# CharliesAlienWhoopF4.net
KiCad netlist of a schematic drawn in EAGLE
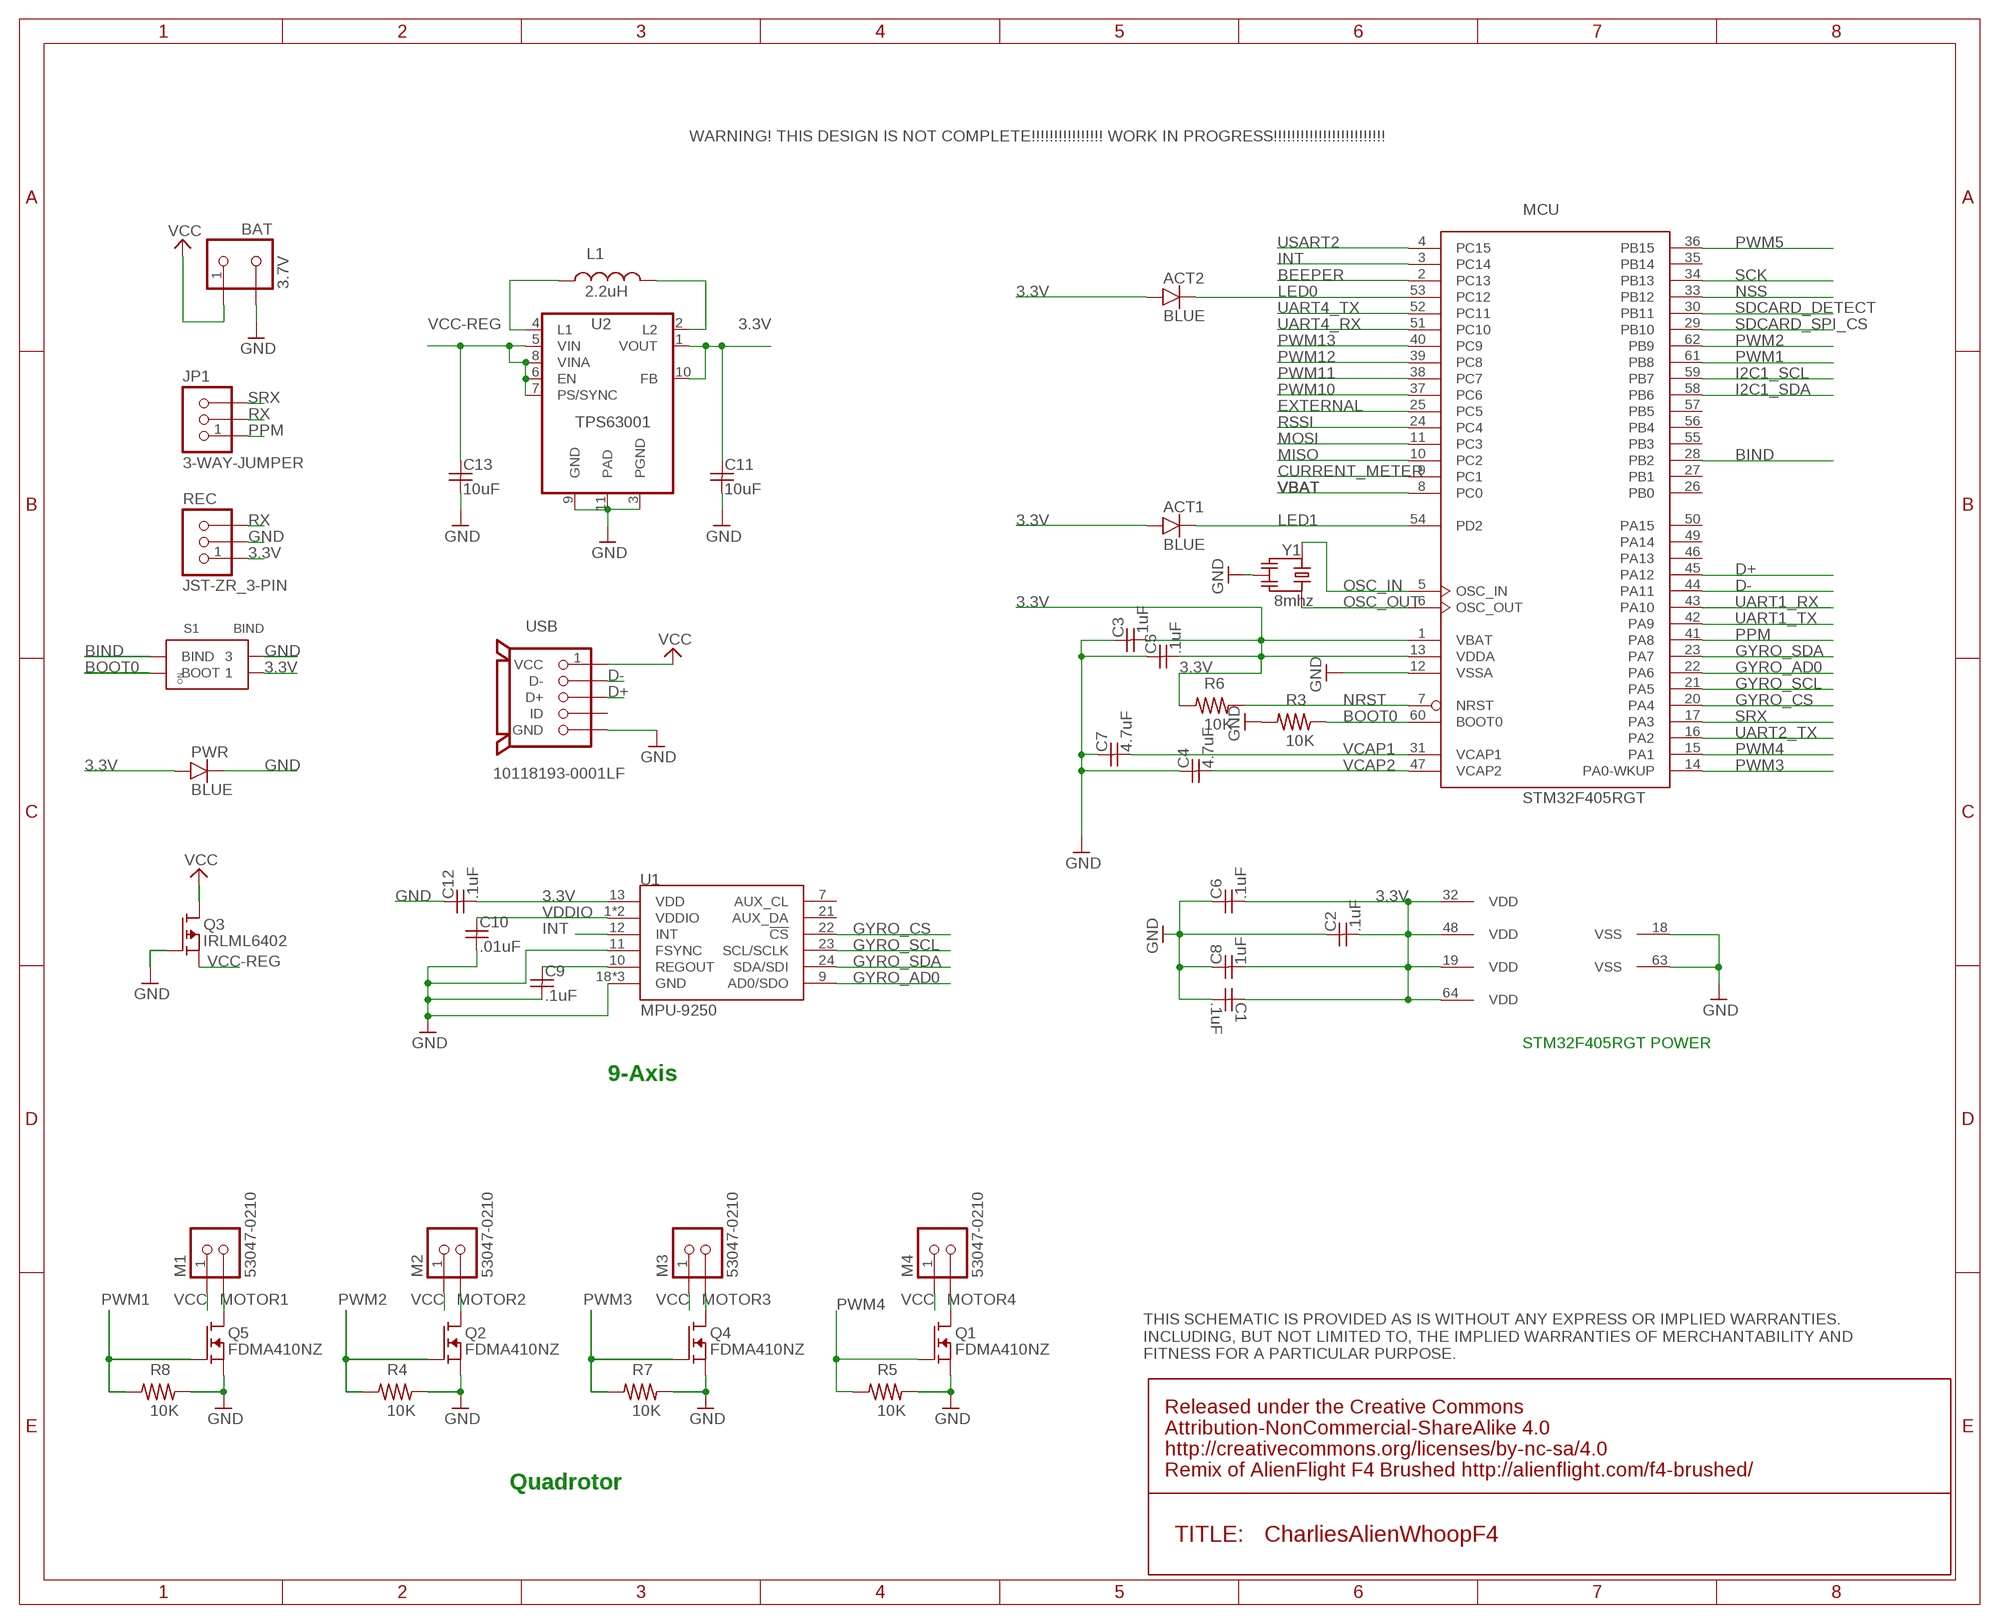
[diagram p0: schematic, sheet 1]

(export (version "E")
  (design (tool "Eeschema 10.0.6"))
  (components
    (comp (ref "ACT1")
      (value "BLUE")
      (footprint "eagle-import:SMD-CHIP-LED-0805")
      (fields (field (name "MF") "Kingbright") (field (name "MPN") "APHCM2012QBC/D-F01"))
      (libsource (lib "eagle-import") (part "SMD-CHIP-LED-0805"))
    )
    (comp (ref "ACT2")
      (value "BLUE")
      (footprint "eagle-import:SMD-CHIP-LED-0805")
      (fields (field (name "MF") "Kingbright") (field (name "MPN") "APHCM2012QBC/D-F01"))
      (libsource (lib "eagle-import") (part "SMD-CHIP-LED-0805"))
    )
    (comp (ref "BAT")
      (value "3.7V")
      (footprint "eagle-import:S2B-PH-K-S")
      (fields (field (name "MF") "JST") (field (name "MPN") "S2B-PH-K-S"))
      (libsource (lib "eagle-import") (part "JST-PH-BAT"))
    )
    (comp (ref "C1")
      (value ".1uF")
      (footprint "eagle-import:MUR-CAP-0603")
      (fields (field (name "MF") "Murata") (field (name "MPN") "GRM188R71C104KA01D"))
      (libsource (lib "eagle-import") (part "CAPACITOR.1UF"))
    )
    (comp (ref "C2")
      (value ".1uF")
      (footprint "eagle-import:MUR-CAP-0603")
      (fields (field (name "MF") "Murata") (field (name "MPN") "GRM188R71C104KA01D"))
      (libsource (lib "eagle-import") (part "CAPACITOR.1UF"))
    )
    (comp (ref "C3")
      (value ".1uF")
      (footprint "eagle-import:MUR-CAP-0603")
      (fields (field (name "MF") "Murata") (field (name "MPN") "GRM188R71C104KA01D"))
      (libsource (lib "eagle-import") (part "CAPACITOR.1UF"))
    )
    (comp (ref "C4")
      (value "4.7uF")
      (footprint "eagle-import:MUR-CAP-0603")
      (fields (field (name "MF") "Murata") (field (name "MPN") "GRJ188C70J475KE11D"))
      (libsource (lib "eagle-import") (part "CAPACITOR4.7UF"))
    )
    (comp (ref "C5")
      (value ".1uF")
      (footprint "eagle-import:MUR-CAP-0603")
      (fields (field (name "MF") "Murata") (field (name "MPN") "GRM188R71C104KA01D"))
      (libsource (lib "eagle-import") (part "CAPACITOR.1UF"))
    )
    (comp (ref "C6")
      (value ".1uF")
      (footprint "eagle-import:MUR-CAP-0603")
      (fields (field (name "MF") "Murata") (field (name "MPN") "GRM188R71C104KA01D"))
      (libsource (lib "eagle-import") (part "CAPACITOR.1UF"))
    )
    (comp (ref "C7")
      (value "4.7uF")
      (footprint "eagle-import:MUR-CAP-0603")
      (fields (field (name "MF") "Murata") (field (name "MPN") "GRJ188C70J475KE11D"))
      (libsource (lib "eagle-import") (part "CAPACITOR4.7UF"))
    )
    (comp (ref "C8")
      (value "1uF")
      (footprint "eagle-import:MUR-CAP-0603")
      (fields (field (name "MF") "Murata") (field (name "MPN") "GRM188R71C105KA12D"))
      (libsource (lib "eagle-import") (part "CAPACITOR1UF"))
    )
    (comp (ref "C9")
      (value ".1uF")
      (footprint "eagle-import:MUR-CAP-0603")
      (fields (field (name "MF") "Murata") (field (name "MPN") "GRM188R71C104KA01D"))
      (libsource (lib "eagle-import") (part "CAPACITOR.1UF"))
    )
    (comp (ref "C10")
      (value ".01uF")
      (footprint "eagle-import:MUR-CAP-0603")
      (fields (field (name "MF") "Murata") (field (name "MPN") "GRM188R71C103KA01D"))
      (libsource (lib "eagle-import") (part "CAPACITOR.01UF"))
    )
    (comp (ref "C11")
      (value "10uF")
      (footprint "eagle-import:YUDEN-CAP-0805")
      (fields (field (name "MF") "Taiyo Yuden") (field (name "MPN") "JMK212AB7106KG-T"))
      (libsource (lib "eagle-import") (part "CAPACITOR10UF"))
    )
    (comp (ref "C12")
      (value ".1uF")
      (footprint "eagle-import:MUR-CAP-0603")
      (fields (field (name "MF") "Murata") (field (name "MPN") "GRM188R71C104KA01D"))
      (libsource (lib "eagle-import") (part "CAPACITOR.1UF"))
    )
    (comp (ref "C13")
      (value "10uF")
      (footprint "eagle-import:YUDEN-CAP-0805")
      (fields (field (name "MF") "Taiyo Yuden") (field (name "MPN") "JMK212AB7106KG-T"))
      (libsource (lib "eagle-import") (part "CAPACITOR10UF"))
    )
    (comp (ref "JP1")
      (value "3-WAY-JUMPER")
      (footprint "eagle-import:3-WAY-JUMPER")
      (libsource (lib "eagle-import") (part "3-WAY-JUMPER"))
    )
    (comp (ref "L1")
      (value "2.2uH")
      (footprint "eagle-import:NR301X")
      (fields (field (name "MF") "Taiyo Yuden") (field (name "MPN") "NR3015T2R2M"))
      (libsource (lib "eagle-import") (part "NR301X"))
    )
    (comp (ref "M1")
      (value "53047-0210")
      (footprint "eagle-import:PICO-53047-02")
      (fields (field (name "MF") "MOLEX"))
      (libsource (lib "eagle-import") (part "PICO-1.25-MOTOR"))
    )
    (comp (ref "M2")
      (value "53047-0210")
      (footprint "eagle-import:PICO-53047-02")
      (fields (field (name "MF") "MOLEX"))
      (libsource (lib "eagle-import") (part "PICO-1.25-MOTOR"))
    )
    (comp (ref "M3")
      (value "53047-0210")
      (footprint "eagle-import:PICO-53047-02")
      (fields (field (name "MF") "MOLEX"))
      (libsource (lib "eagle-import") (part "PICO-1.25-MOTOR"))
    )
    (comp (ref "M4")
      (value "53047-0210")
      (footprint "eagle-import:PICO-53047-02")
      (fields (field (name "MF") "MOLEX"))
      (libsource (lib "eagle-import") (part "PICO-1.25-MOTOR"))
    )
    (comp (ref "MCU")
      (value "STM32F405RGT")
      (footprint "eagle-import:LQFP64")
      (libsource (lib "eagle-import") (part "STM32F405RTG"))
    )
    (comp (ref "PWR")
      (value "BLUE")
      (footprint "eagle-import:SMD-CHIP-LED-0805")
      (fields (field (name "MF") "Kingbright") (field (name "MPN") "APHCM2012QBC/D-F01"))
      (libsource (lib "eagle-import") (part "SMD-CHIP-LED-0805"))
    )
    (comp (ref "Q1")
      (value "FDMA410NZ")
      (footprint "eagle-import:MICROFET-2X2")
      (fields (field (name "MF") "Fairchild"))
      (libsource (lib "eagle-import") (part "FDMA410NZ"))
    )
    (comp (ref "Q2")
      (value "FDMA410NZ")
      (footprint "eagle-import:MICROFET-2X2")
      (fields (field (name "MF") "Fairchild"))
      (libsource (lib "eagle-import") (part "FDMA410NZ"))
    )
    (comp (ref "Q3")
      (value "IRLML6402")
      (footprint "eagle-import:SOT-23")
      (fields (field (name "MF") "IR"))
      (libsource (lib "eagle-import") (part "MOSFET-P"))
    )
    (comp (ref "Q4")
      (value "FDMA410NZ")
      (footprint "eagle-import:MICROFET-2X2")
      (fields (field (name "MF") "Fairchild"))
      (libsource (lib "eagle-import") (part "FDMA410NZ"))
    )
    (comp (ref "Q5")
      (value "FDMA410NZ")
      (footprint "eagle-import:MICROFET-2X2")
      (fields (field (name "MF") "Fairchild"))
      (libsource (lib "eagle-import") (part "FDMA410NZ"))
    )
    (comp (ref "R3")
      (value "10K")
      (footprint "eagle-import:VISH-RES-0603")
      (fields (field (name "MF") "Vishay") (field (name "MPN") "CRCW060310K0FKEAHP"))
      (libsource (lib "eagle-import") (part "RESISTOR10K"))
    )
    (comp (ref "R4")
      (value "10K")
      (footprint "eagle-import:VISH-RES-0603")
      (fields (field (name "MF") "Vishay") (field (name "MPN") "CRCW060310K0FKEAHP"))
      (libsource (lib "eagle-import") (part "RESISTOR10K"))
    )
    (comp (ref "R5")
      (value "10K")
      (footprint "eagle-import:VISH-RES-0603")
      (fields (field (name "MF") "Vishay") (field (name "MPN") "CRCW060310K0FKEAHP"))
      (libsource (lib "eagle-import") (part "RESISTOR10K"))
    )
    (comp (ref "R6")
      (value "10K")
      (footprint "eagle-import:VISH-RES-0603")
      (fields (field (name "MF") "Vishay") (field (name "MPN") "CRCW060310K0FKEAHP"))
      (libsource (lib "eagle-import") (part "RESISTOR10K"))
    )
    (comp (ref "R7")
      (value "10K")
      (footprint "eagle-import:VISH-RES-0603")
      (fields (field (name "MF") "Vishay") (field (name "MPN") "CRCW060310K0FKEAHP"))
      (libsource (lib "eagle-import") (part "RESISTOR10K"))
    )
    (comp (ref "R8")
      (value "10K")
      (footprint "eagle-import:VISH-RES-0603")
      (fields (field (name "MF") "Vishay") (field (name "MPN") "CRCW060310K0FKEAHP"))
      (libsource (lib "eagle-import") (part "RESISTOR10K"))
    )
    (comp (ref "REC")
      (value "JST-ZR_3-PIN")
      (footprint "eagle-import:S3B-ZR")
      (fields (field (name "MF") "JST") (field (name "MPN") "S3B-ZR"))
      (libsource (lib "eagle-import") (part "JST-ZR_3-PIN"))
    )
    (comp (ref "S1")
      (value "BIND")
      (footprint "eagle-import:A6H-2101")
      (libsource (lib "eagle-import") (part "2POS-DIP-SWITCH"))
    )
    (comp (ref "U1")
      (value "MPU-9250")
      (footprint "eagle-import:QFN24_PAD")
      (libsource (lib "eagle-import") (part "MPU-9250"))
    )
    (comp (ref "U2")
      (value "TPS63001")
      (footprint "eagle-import:VSON-N10")
      (fields (field (name "MF") "TI") (field (name "MPN") "TPS63001DRCR"))
      (libsource (lib "eagle-import") (part "TPS630XX-TPS63001"))
    )
    (comp (ref "USB")
      (value "10118193-0001LF")
      (footprint "eagle-import:10118193-0001LF")
      (fields (field (name "MF") "FCI"))
      (libsource (lib "eagle-import") (part "USB-MICRO-B-FCI"))
    )
    (comp (ref "Y1")
      (value "8mhz")
      (footprint "eagle-import:RESONATOR_8")
      (fields (field (name "MF") "Murata") (field (name "MPN") "CSTCE8M00G55-R0"))
      (libsource (lib "eagle-import") (part "RESONATOR8MHZ"))
    )
  )
  (nets
    (net (code "1") (name "/3.3V") (class "Default")
      (node (ref "ACT1") (pin "A") (pinfunction "A_A") (pintype "passive"))
      (node (ref "ACT2") (pin "A") (pinfunction "A_A") (pintype "passive"))
      (node (ref "C1") (pin "1") (pinfunction "1_1") (pintype "passive"))
      (node (ref "C11") (pin "1") (pinfunction "1_1") (pintype "passive"))
      (node (ref "C12") (pin "2") (pinfunction "2_2") (pintype "passive"))
      (node (ref "C2") (pin "2") (pinfunction "2_2") (pintype "passive"))
      (node (ref "C3") (pin "2") (pinfunction "2_2") (pintype "passive"))
      (node (ref "C5") (pin "2") (pinfunction "2_2") (pintype "passive"))
      (node (ref "C6") (pin "2") (pinfunction "2_2") (pintype "passive"))
      (node (ref "C8") (pin "2") (pinfunction "2_2") (pintype "passive"))
      (node (ref "MCU") (pin "1") (pinfunction "VBAT_1") (pintype "power_in"))
      (node (ref "MCU") (pin "13") (pinfunction "VDDA_13") (pintype "power_in"))
      (node (ref "MCU") (pin "19") (pinfunction "VDD_19") (pintype "power_in"))
      (node (ref "MCU") (pin "32") (pinfunction "VDD_32") (pintype "power_in"))
      (node (ref "MCU") (pin "48") (pinfunction "VDD_48") (pintype "power_in"))
      (node (ref "MCU") (pin "64") (pinfunction "VDD_64") (pintype "power_in"))
      (node (ref "PWR") (pin "A") (pinfunction "A_A") (pintype "passive"))
      (node (ref "R6") (pin "2") (pinfunction "2_2") (pintype "passive"))
      (node (ref "REC") (pin "1") (pinfunction "1_1") (pintype "bidirectional"))
      (node (ref "S1") (pin "BOOT_1") (pinfunction "1_BOOT_1") (pintype "bidirectional"))
      (node (ref "U1") (pin "13") (pinfunction "VDD_13") (pintype "bidirectional"))
      (node (ref "U2") (pin "1") (pinfunction "VOUT_1") (pintype "bidirectional"))
      (node (ref "U2") (pin "10") (pinfunction "FB_10") (pintype "bidirectional"))
    )
    (net (code "2") (name "/BEEPER") (class "Default")
      (node (ref "MCU") (pin "2") (pinfunction "PC13_2") (pintype "bidirectional"))
    )
    (net (code "3") (name "/BIND") (class "Default")
      (node (ref "MCU") (pin "28") (pinfunction "PB2_28") (pintype "bidirectional"))
      (node (ref "S1") (pin "BIND_2") (pinfunction "BIND_BIND_2") (pintype "bidirectional"))
    )
    (net (code "4") (name "/BOOT0") (class "Default")
      (node (ref "MCU") (pin "60") (pinfunction "BOOT0_60") (pintype "input"))
      (node (ref "R3") (pin "1") (pinfunction "1_1") (pintype "passive"))
      (node (ref "S1") (pin "BOOT_2") (pinfunction "BOOT_BOOT_2") (pintype "bidirectional"))
    )
    (net (code "5") (name "/CURRENT_METER") (class "Default")
      (node (ref "MCU") (pin "9") (pinfunction "PC1_9") (pintype "bidirectional"))
    )
    (net (code "6") (name "/D+") (class "Default")
      (node (ref "MCU") (pin "45") (pinfunction "PA12_45") (pintype "bidirectional"))
      (node (ref "USB") (pin "3") (pinfunction "D+_3") (pintype "passive"))
    )
    (net (code "7") (name "/D-") (class "Default")
      (node (ref "MCU") (pin "44") (pinfunction "PA11_44") (pintype "bidirectional"))
      (node (ref "USB") (pin "2") (pinfunction "D-_2") (pintype "passive"))
    )
    (net (code "8") (name "/EXTERNAL") (class "Default")
      (node (ref "MCU") (pin "25") (pinfunction "PC5_25") (pintype "bidirectional"))
    )
    (net (code "9") (name "/GYRO_AD0") (class "Default")
      (node (ref "MCU") (pin "22") (pinfunction "PA6_22") (pintype "bidirectional"))
      (node (ref "U1") (pin "9") (pinfunction "AD0/SDO_9") (pintype "bidirectional"))
    )
    (net (code "10") (name "/GYRO_CS") (class "Default")
      (node (ref "MCU") (pin "20") (pinfunction "PA4_20") (pintype "bidirectional"))
      (node (ref "U1") (pin "22") (pinfunction "~{CS}_22") (pintype "bidirectional"))
    )
    (net (code "11") (name "/GYRO_SCL") (class "Default")
      (node (ref "MCU") (pin "21") (pinfunction "PA5_21") (pintype "bidirectional"))
      (node (ref "U1") (pin "23") (pinfunction "SCL/SCLK_23") (pintype "bidirectional"))
    )
    (net (code "12") (name "/GYRO_SDA") (class "Default")
      (node (ref "MCU") (pin "23") (pinfunction "PA7_23") (pintype "bidirectional"))
      (node (ref "U1") (pin "24") (pinfunction "SDA/SDI_24") (pintype "bidirectional"))
    )
    (net (code "13") (name "/I2C1_SCL") (class "Default")
      (node (ref "MCU") (pin "59") (pinfunction "PB7_59") (pintype "bidirectional"))
    )
    (net (code "14") (name "/I2C1_SDA") (class "Default")
      (node (ref "MCU") (pin "58") (pinfunction "PB6_58") (pintype "bidirectional"))
    )
    (net (code "15") (name "/INT") (class "Default")
      (node (ref "MCU") (pin "3") (pinfunction "PC14_3") (pintype "bidirectional"))
      (node (ref "U1") (pin "12") (pinfunction "INT_12") (pintype "bidirectional"))
    )
    (net (code "16") (name "/LED0") (class "Default")
      (node (ref "ACT2") (pin "C") (pinfunction "C_C") (pintype "passive"))
      (node (ref "MCU") (pin "53") (pinfunction "PC12_53") (pintype "bidirectional"))
    )
    (net (code "17") (name "/LED1") (class "Default")
      (node (ref "ACT1") (pin "C") (pinfunction "C_C") (pintype "passive"))
      (node (ref "MCU") (pin "54") (pinfunction "PD2_54") (pintype "bidirectional"))
    )
    (net (code "18") (name "/MISO") (class "Default")
      (node (ref "MCU") (pin "10") (pinfunction "PC2_10") (pintype "bidirectional"))
    )
    (net (code "19") (name "/MOSI") (class "Default")
      (node (ref "MCU") (pin "11") (pinfunction "PC3_11") (pintype "bidirectional"))
    )
    (net (code "20") (name "/MOTOR1") (class "Default")
      (node (ref "M1") (pin "2") (pinfunction "2_2") (pintype "passive"))
      (node (ref "Q5") (pin "D") (pinfunction "D_D") (pintype "bidirectional"))
      (node (ref "Q5") (pin "D1") (pinfunction "D_D1") (pintype "bidirectional"))
      (node (ref "Q5") (pin "D2") (pinfunction "D_D2") (pintype "bidirectional"))
      (node (ref "Q5") (pin "D3") (pinfunction "D_D3") (pintype "bidirectional"))
      (node (ref "Q5") (pin "D4") (pinfunction "D_D4") (pintype "bidirectional"))
    )
    (net (code "21") (name "/MOTOR2") (class "Default")
      (node (ref "M2") (pin "2") (pinfunction "2_2") (pintype "passive"))
      (node (ref "Q2") (pin "D") (pinfunction "D_D") (pintype "bidirectional"))
      (node (ref "Q2") (pin "D1") (pinfunction "D_D1") (pintype "bidirectional"))
      (node (ref "Q2") (pin "D2") (pinfunction "D_D2") (pintype "bidirectional"))
      (node (ref "Q2") (pin "D3") (pinfunction "D_D3") (pintype "bidirectional"))
      (node (ref "Q2") (pin "D4") (pinfunction "D_D4") (pintype "bidirectional"))
    )
    (net (code "22") (name "/MOTOR3") (class "Default")
      (node (ref "M3") (pin "2") (pinfunction "2_2") (pintype "passive"))
      (node (ref "Q4") (pin "D") (pinfunction "D_D") (pintype "bidirectional"))
      (node (ref "Q4") (pin "D1") (pinfunction "D_D1") (pintype "bidirectional"))
      (node (ref "Q4") (pin "D2") (pinfunction "D_D2") (pintype "bidirectional"))
      (node (ref "Q4") (pin "D3") (pinfunction "D_D3") (pintype "bidirectional"))
      (node (ref "Q4") (pin "D4") (pinfunction "D_D4") (pintype "bidirectional"))
    )
    (net (code "23") (name "/MOTOR4") (class "Default")
      (node (ref "M4") (pin "2") (pinfunction "2_2") (pintype "passive"))
      (node (ref "Q1") (pin "D") (pinfunction "D_D") (pintype "bidirectional"))
      (node (ref "Q1") (pin "D1") (pinfunction "D_D1") (pintype "bidirectional"))
      (node (ref "Q1") (pin "D2") (pinfunction "D_D2") (pintype "bidirectional"))
      (node (ref "Q1") (pin "D3") (pinfunction "D_D3") (pintype "bidirectional"))
      (node (ref "Q1") (pin "D4") (pinfunction "D_D4") (pintype "bidirectional"))
    )
    (net (code "24") (name "/NRST") (class "Default")
      (node (ref "MCU") (pin "7") (pinfunction "NRST_7") (pintype "bidirectional"))
      (node (ref "R6") (pin "1") (pinfunction "1_1") (pintype "passive"))
    )
    (net (code "25") (name "/NSS") (class "Default")
      (node (ref "MCU") (pin "33") (pinfunction "PB12_33") (pintype "bidirectional"))
    )
    (net (code "26") (name "/OSC_IN") (class "Default")
      (node (ref "MCU") (pin "5") (pinfunction "OSC_IN_5") (pintype "bidirectional"))
      (node (ref "Y1") (pin "1") (pinfunction "1_1") (pintype "passive"))
    )
    (net (code "27") (name "/OSC_OUT") (class "Default")
      (node (ref "MCU") (pin "6") (pinfunction "OSC_OUT_6") (pintype "bidirectional"))
      (node (ref "Y1") (pin "3") (pinfunction "3_3") (pintype "passive"))
    )
    (net (code "28") (name "/PPM") (class "Default")
      (node (ref "JP1") (pin "1") (pinfunction "1_1") (pintype "bidirectional"))
      (node (ref "MCU") (pin "41") (pinfunction "PA8_41") (pintype "bidirectional"))
    )
    (net (code "29") (name "/PWM1") (class "Default")
      (node (ref "MCU") (pin "61") (pinfunction "PB8_61") (pintype "bidirectional"))
      (node (ref "Q5") (pin "G") (pinfunction "G_G") (pintype "bidirectional"))
      (node (ref "R8") (pin "2") (pinfunction "2_2") (pintype "passive"))
    )
    (net (code "30") (name "/PWM2") (class "Default")
      (node (ref "MCU") (pin "62") (pinfunction "PB9_62") (pintype "bidirectional"))
      (node (ref "Q2") (pin "G") (pinfunction "G_G") (pintype "bidirectional"))
      (node (ref "R4") (pin "2") (pinfunction "2_2") (pintype "passive"))
    )
    (net (code "31") (name "/PWM3") (class "Default")
      (node (ref "MCU") (pin "14") (pinfunction "PA0-WKUP_14") (pintype "bidirectional"))
      (node (ref "Q4") (pin "G") (pinfunction "G_G") (pintype "bidirectional"))
      (node (ref "R7") (pin "2") (pinfunction "2_2") (pintype "passive"))
    )
    (net (code "32") (name "/PWM4") (class "Default")
      (node (ref "MCU") (pin "15") (pinfunction "PA1_15") (pintype "bidirectional"))
      (node (ref "Q1") (pin "G") (pinfunction "G_G") (pintype "bidirectional"))
      (node (ref "R5") (pin "2") (pinfunction "2_2") (pintype "passive"))
    )
    (net (code "33") (name "/PWM5") (class "Default")
      (node (ref "MCU") (pin "36") (pinfunction "PB15_36") (pintype "bidirectional"))
    )
    (net (code "34") (name "/PWM10") (class "Default")
      (node (ref "MCU") (pin "37") (pinfunction "PC6_37") (pintype "bidirectional"))
    )
    (net (code "35") (name "/PWM11") (class "Default")
      (node (ref "MCU") (pin "38") (pinfunction "PC7_38") (pintype "bidirectional"))
    )
    (net (code "36") (name "/PWM12") (class "Default")
      (node (ref "MCU") (pin "39") (pinfunction "PC8_39") (pintype "bidirectional"))
    )
    (net (code "37") (name "/PWM13") (class "Default")
      (node (ref "MCU") (pin "40") (pinfunction "PC9_40") (pintype "bidirectional"))
    )
    (net (code "38") (name "/RSSI") (class "Default")
      (node (ref "MCU") (pin "24") (pinfunction "PC4_24") (pintype "bidirectional"))
    )
    (net (code "39") (name "/RX") (class "Default")
      (node (ref "JP1") (pin "2") (pinfunction "2_2") (pintype "bidirectional"))
      (node (ref "REC") (pin "3") (pinfunction "3_3") (pintype "bidirectional"))
    )
    (net (code "40") (name "/SCK") (class "Default")
      (node (ref "MCU") (pin "34") (pinfunction "PB13_34") (pintype "bidirectional"))
    )
    (net (code "41") (name "/SDCARD_DETECT") (class "Default")
      (node (ref "MCU") (pin "30") (pinfunction "PB11_30") (pintype "bidirectional"))
    )
    (net (code "42") (name "/SDCARD_SPI_CS") (class "Default")
      (node (ref "MCU") (pin "29") (pinfunction "PB10_29") (pintype "bidirectional"))
    )
    (net (code "43") (name "/SRX") (class "Default")
      (node (ref "JP1") (pin "3") (pinfunction "3_3") (pintype "bidirectional"))
      (node (ref "MCU") (pin "17") (pinfunction "PA3_17") (pintype "bidirectional"))
    )
    (net (code "44") (name "/UART1_RX") (class "Default")
      (node (ref "MCU") (pin "43") (pinfunction "PA10_43") (pintype "bidirectional"))
    )
    (net (code "45") (name "/UART1_TX") (class "Default")
      (node (ref "MCU") (pin "42") (pinfunction "PA9_42") (pintype "bidirectional"))
    )
    (net (code "46") (name "/UART2_TX") (class "Default")
      (node (ref "MCU") (pin "16") (pinfunction "PA2_16") (pintype "bidirectional"))
    )
    (net (code "47") (name "/UART4_RX") (class "Default")
      (node (ref "MCU") (pin "51") (pinfunction "PC10_51") (pintype "bidirectional"))
    )
    (net (code "48") (name "/UART4_TX") (class "Default")
      (node (ref "MCU") (pin "52") (pinfunction "PC11_52") (pintype "bidirectional"))
    )
    (net (code "49") (name "/USART2") (class "Default")
      (node (ref "MCU") (pin "4") (pinfunction "PC15_4") (pintype "bidirectional"))
    )
    (net (code "50") (name "/VBAT") (class "Default")
      (node (ref "MCU") (pin "8") (pinfunction "PC0_8") (pintype "bidirectional"))
    )
    (net (code "51") (name "/VCAP1") (class "Default")
      (node (ref "C7") (pin "2") (pinfunction "2_2") (pintype "passive"))
      (node (ref "MCU") (pin "31") (pinfunction "VCAP1_31") (pintype "power_in"))
    )
    (net (code "52") (name "/VCAP2") (class "Default")
      (node (ref "C4") (pin "2") (pinfunction "2_2") (pintype "passive"))
      (node (ref "MCU") (pin "47") (pinfunction "VCAP2_47") (pintype "power_in"))
    )
    (net (code "53") (name "/VCC-REG") (class "Default")
      (node (ref "C13") (pin "1") (pinfunction "1_1") (pintype "passive"))
      (node (ref "Q3") (pin "2") (pinfunction "S_2") (pintype "bidirectional"))
      (node (ref "U2") (pin "5") (pinfunction "VIN_5") (pintype "bidirectional"))
      (node (ref "U2") (pin "6") (pinfunction "EN_6") (pintype "bidirectional"))
      (node (ref "U2") (pin "7") (pinfunction "PS/SYNC_7") (pintype "bidirectional"))
      (node (ref "U2") (pin "8") (pinfunction "VINA_8") (pintype "bidirectional"))
    )
    (net (code "54") (name "/VDDIO") (class "Default")
      (node (ref "C10") (pin "1") (pinfunction "1_1") (pintype "passive"))
      (node (ref "U1") (pin "1") (pinfunction "VDDIO_1") (pintype "bidirectional"))
      (node (ref "U1") (pin "8") (pinfunction "VDDIO_8") (pintype "bidirectional"))
    )
    (net (code "55") (name "GND") (class "Default")
      (node (ref "BAT") (pin "2") (pinfunction "2_2") (pintype "bidirectional"))
      (node (ref "C1") (pin "2") (pinfunction "2_2") (pintype "passive"))
      (node (ref "C10") (pin "2") (pinfunction "2_2") (pintype "passive"))
      (node (ref "C11") (pin "2") (pinfunction "2_2") (pintype "passive"))
      (node (ref "C12") (pin "1") (pinfunction "1_1") (pintype "passive"))
      (node (ref "C13") (pin "2") (pinfunction "2_2") (pintype "passive"))
      (node (ref "C2") (pin "1") (pinfunction "1_1") (pintype "passive"))
      (node (ref "C3") (pin "1") (pinfunction "1_1") (pintype "passive"))
      (node (ref "C4") (pin "1") (pinfunction "1_1") (pintype "passive"))
      (node (ref "C5") (pin "1") (pinfunction "1_1") (pintype "passive"))
      (node (ref "C6") (pin "1") (pinfunction "1_1") (pintype "passive"))
      (node (ref "C7") (pin "1") (pinfunction "1_1") (pintype "passive"))
      (node (ref "C8") (pin "1") (pinfunction "1_1") (pintype "passive"))
      (node (ref "C9") (pin "2") (pinfunction "2_2") (pintype "passive"))
      (node (ref "MCU") (pin "12") (pinfunction "VSSA_12") (pintype "power_in"))
      (node (ref "MCU") (pin "18") (pinfunction "VSS_18") (pintype "power_in"))
      (node (ref "MCU") (pin "63") (pinfunction "VSS_63") (pintype "power_in"))
      (node (ref "PWR") (pin "C") (pinfunction "C_C") (pintype "passive"))
      (node (ref "Q1") (pin "S") (pinfunction "S_S") (pintype "bidirectional"))
      (node (ref "Q1") (pin "S1") (pinfunction "S_S1") (pintype "bidirectional"))
      (node (ref "Q2") (pin "S") (pinfunction "S_S") (pintype "bidirectional"))
      (node (ref "Q2") (pin "S1") (pinfunction "S_S1") (pintype "bidirectional"))
      (node (ref "Q3") (pin "1") (pinfunction "G_1") (pintype "bidirectional"))
      (node (ref "Q4") (pin "S") (pinfunction "S_S") (pintype "bidirectional"))
      (node (ref "Q4") (pin "S1") (pinfunction "S_S1") (pintype "bidirectional"))
      (node (ref "Q5") (pin "S") (pinfunction "S_S") (pintype "bidirectional"))
      (node (ref "Q5") (pin "S1") (pinfunction "S_S1") (pintype "bidirectional"))
      (node (ref "R3") (pin "2") (pinfunction "2_2") (pintype "passive"))
      (node (ref "R4") (pin "1") (pinfunction "1_1") (pintype "passive"))
      (node (ref "R5") (pin "1") (pinfunction "1_1") (pintype "passive"))
      (node (ref "R7") (pin "1") (pinfunction "1_1") (pintype "passive"))
      (node (ref "R8") (pin "1") (pinfunction "1_1") (pintype "passive"))
      (node (ref "REC") (pin "2") (pinfunction "2_2") (pintype "bidirectional"))
      (node (ref "S1") (pin "BIND_1") (pinfunction "3_BIND_1") (pintype "bidirectional"))
      (node (ref "U1") (pin "11") (pinfunction "FSYNC_11") (pintype "bidirectional"))
      (node (ref "U1") (pin "18") (pinfunction "GND_18") (pintype "bidirectional"))
      (node (ref "U1") (pin "20") (pinfunction "GND_20") (pintype "bidirectional"))
      (node (ref "U1") (pin "CENTER") (pinfunction "GND_CENTER") (pintype "bidirectional"))
      (node (ref "U2") (pin "11") (pinfunction "PAD_11") (pintype "bidirectional"))
      (node (ref "U2") (pin "3") (pinfunction "PGND_3") (pintype "bidirectional"))
      (node (ref "U2") (pin "9") (pinfunction "GND_9") (pintype "bidirectional"))
      (node (ref "USB") (pin "5") (pinfunction "GND_5") (pintype "passive"))
      (node (ref "USB") (pin "GND") (pinfunction "GND_GND") (pintype "passive"))
      (node (ref "USB") (pin "GND2") (pinfunction "GND_GND2") (pintype "passive"))
      (node (ref "USB") (pin "HOLE1") (pinfunction "GND_HOLE1") (pintype "passive"))
      (node (ref "USB") (pin "HOLE2") (pinfunction "GND_HOLE2") (pintype "passive"))
      (node (ref "Y1") (pin "2") (pinfunction "2_2") (pintype "passive"))
    )
    (net (code "56") (name "Net-(U1-REGOUT)") (class "Default")
      (node (ref "C9") (pin "1") (pinfunction "1_1") (pintype "passive"))
      (node (ref "U1") (pin "10") (pinfunction "REGOUT_10") (pintype "bidirectional"))
    )
    (net (code "57") (name "Net-(U2-L1)") (class "Default")
      (node (ref "L1") (pin "1") (pinfunction "1_1") (pintype "passive"))
      (node (ref "U2") (pin "4") (pinfunction "L1_4") (pintype "bidirectional"))
    )
    (net (code "58") (name "Net-(U2-L2)") (class "Default")
      (node (ref "L1") (pin "2") (pinfunction "2_2") (pintype "passive"))
      (node (ref "U2") (pin "2") (pinfunction "L2_2") (pintype "bidirectional"))
    )
    (net (code "59") (name "VCC") (class "Default")
      (node (ref "BAT") (pin "1") (pinfunction "1_1") (pintype "bidirectional"))
      (node (ref "M1") (pin "1") (pinfunction "1_1") (pintype "passive"))
      (node (ref "M2") (pin "1") (pinfunction "1_1") (pintype "passive"))
      (node (ref "M3") (pin "1") (pinfunction "1_1") (pintype "passive"))
      (node (ref "M4") (pin "1") (pinfunction "1_1") (pintype "passive"))
      (node (ref "Q3") (pin "3") (pinfunction "D_3") (pintype "bidirectional"))
      (node (ref "USB") (pin "1") (pinfunction "VCC_1") (pintype "passive"))
    )
    (net (code "60") (name "unconnected-(MCUA-PA13-Pad46)") (class "Default")
      (node (ref "MCU") (pin "46") (pinfunction "PA13_46") (pintype "bidirectional"))
    )
    (net (code "61") (name "unconnected-(MCUA-PA14-Pad49)") (class "Default")
      (node (ref "MCU") (pin "49") (pinfunction "PA14_49") (pintype "bidirectional"))
    )
    (net (code "62") (name "unconnected-(MCUA-PA15-Pad50)") (class "Default")
      (node (ref "MCU") (pin "50") (pinfunction "PA15_50") (pintype "bidirectional"))
    )
    (net (code "63") (name "unconnected-(MCUA-PB0-Pad26)") (class "Default")
      (node (ref "MCU") (pin "26") (pinfunction "PB0_26") (pintype "bidirectional"))
    )
    (net (code "64") (name "unconnected-(MCUA-PB1-Pad27)") (class "Default")
      (node (ref "MCU") (pin "27") (pinfunction "PB1_27") (pintype "bidirectional"))
    )
    (net (code "65") (name "unconnected-(MCUA-PB3-Pad55)") (class "Default")
      (node (ref "MCU") (pin "55") (pinfunction "PB3_55") (pintype "bidirectional"))
    )
    (net (code "66") (name "unconnected-(MCUA-PB4-Pad56)") (class "Default")
      (node (ref "MCU") (pin "56") (pinfunction "PB4_56") (pintype "bidirectional"))
    )
    (net (code "67") (name "unconnected-(MCUA-PB5-Pad57)") (class "Default")
      (node (ref "MCU") (pin "57") (pinfunction "PB5_57") (pintype "bidirectional"))
    )
    (net (code "68") (name "unconnected-(MCUA-PB14-Pad35)") (class "Default")
      (node (ref "MCU") (pin "35") (pinfunction "PB14_35") (pintype "bidirectional"))
    )
    (net (code "69") (name "unconnected-(U1-AUX_CL-Pad7)") (class "Default")
      (node (ref "U1") (pin "7") (pinfunction "AUX_CL_7") (pintype "bidirectional"))
    )
    (net (code "70") (name "unconnected-(U1-AUX_DA-Pad21)") (class "Default")
      (node (ref "U1") (pin "21") (pinfunction "AUX_DA_21") (pintype "bidirectional"))
    )
    (net (code "71") (name "unconnected-(USB-ID-Pad4)") (class "Default")
      (node (ref "USB") (pin "4") (pinfunction "ID_4") (pintype "passive"))
    )
  )
)
